# ClockGen.net
KiCad netlist of a schematic drawn in Altium Designer
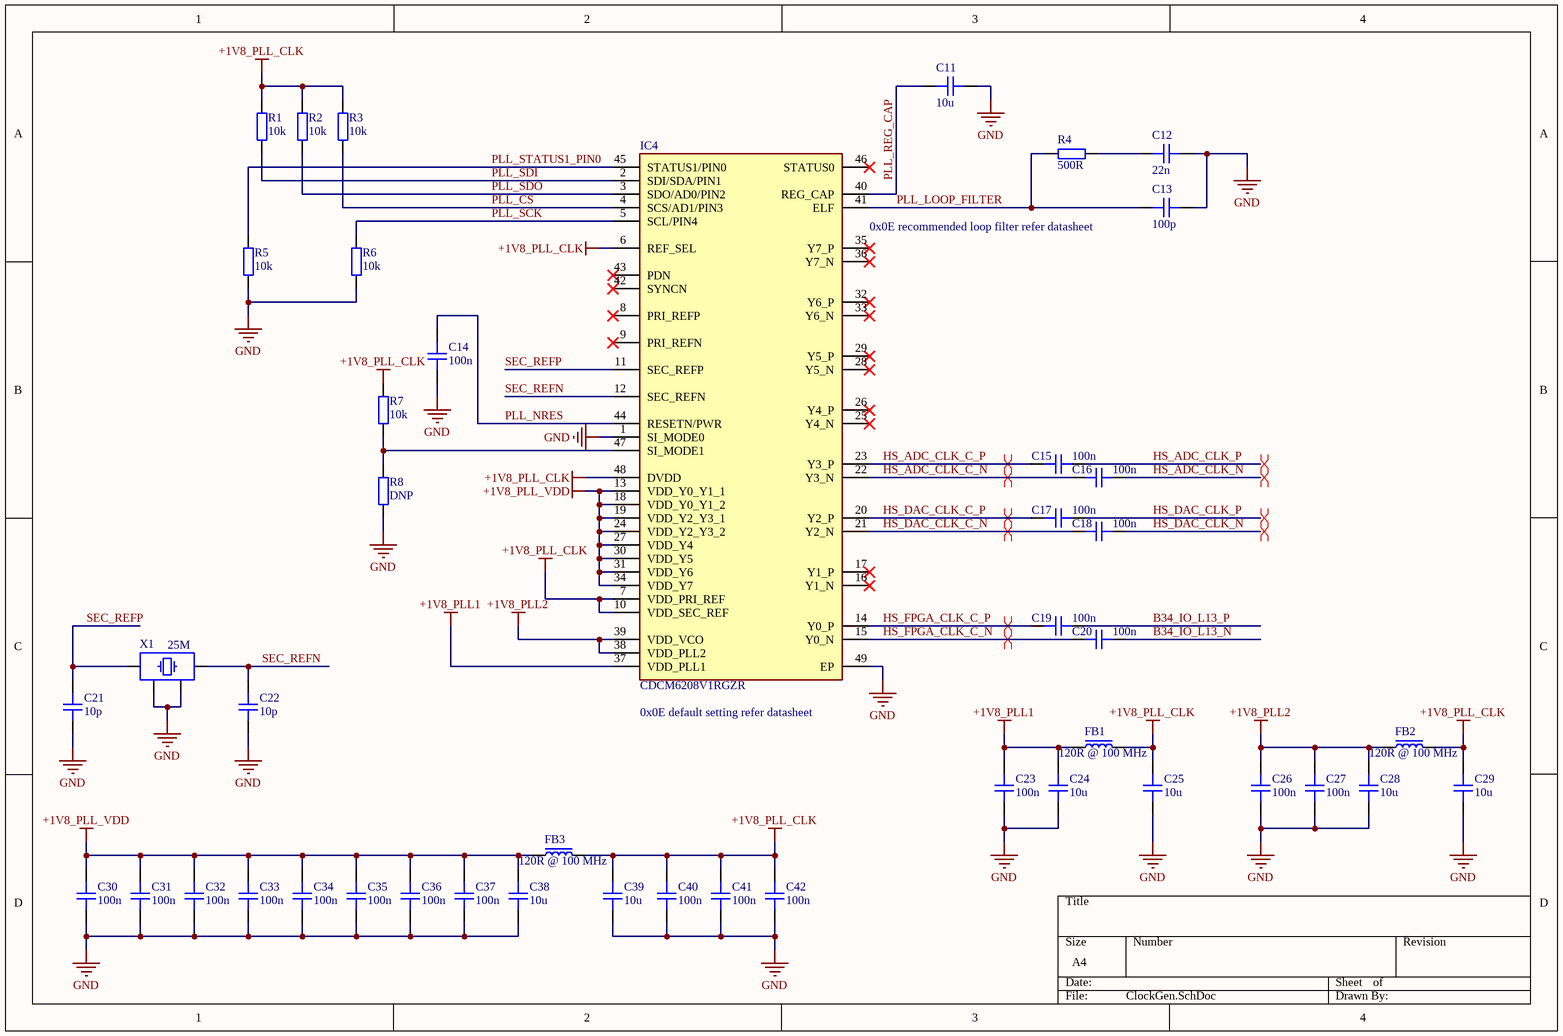
[diagram p0: ClockGen.SchDoc]

(export (version "E")
  (design (tool "Eeschema 10.0.6"))
  (components
    (comp (ref "C11")
      (value "10u")
      (footprint "CAP_0603")
      (description "Capacitor SMD 0603")
      (libsource (lib "Schematic-Lib-PhilsLab") (part "CAP_0603"))
    )
    (comp (ref "C12")
      (value "22n")
      (footprint "CAP_0402")
      (description "Capacitor SMD 0402")
      (libsource (lib "Schematic-Lib-PhilsLab") (part "CAP_0402"))
    )
    (comp (ref "C13")
      (value "100p")
      (footprint "CAP_0402")
      (description "Capacitor SMD 0402")
      (libsource (lib "Schematic-Lib-PhilsLab") (part "CAP_0402"))
    )
    (comp (ref "C14")
      (value "100n")
      (footprint "CAP_0402")
      (description "Capacitor SMD 0402")
      (libsource (lib "Schematic-Lib-PhilsLab") (part "CAP_0402"))
    )
    (comp (ref "C15")
      (value "100n")
      (footprint "CAP_0402")
      (description "Capacitor SMD 0402")
      (libsource (lib "Schematic-Lib-PhilsLab") (part "CAP_0402"))
    )
    (comp (ref "C16")
      (value "100n")
      (footprint "CAP_0402")
      (description "Capacitor SMD 0402")
      (libsource (lib "Schematic-Lib-PhilsLab") (part "CAP_0402"))
    )
    (comp (ref "C17")
      (value "100n")
      (footprint "CAP_0402")
      (description "Capacitor SMD 0402")
      (libsource (lib "Schematic-Lib-PhilsLab") (part "CAP_0402"))
    )
    (comp (ref "C18")
      (value "100n")
      (footprint "CAP_0402")
      (description "Capacitor SMD 0402")
      (libsource (lib "Schematic-Lib-PhilsLab") (part "CAP_0402"))
    )
    (comp (ref "C19")
      (value "100n")
      (footprint "CAP_0402")
      (description "Capacitor SMD 0402")
      (libsource (lib "Schematic-Lib-PhilsLab") (part "CAP_0402"))
    )
    (comp (ref "C20")
      (value "100n")
      (footprint "CAP_0402")
      (description "Capacitor SMD 0402")
      (libsource (lib "Schematic-Lib-PhilsLab") (part "CAP_0402"))
    )
    (comp (ref "C21")
      (value "10p")
      (footprint "CAP_0402")
      (description "Capacitor SMD 0402")
      (libsource (lib "Schematic-Lib-PhilsLab") (part "CAP_0402"))
    )
    (comp (ref "C22")
      (value "10p")
      (footprint "CAP_0402")
      (description "Capacitor SMD 0402")
      (libsource (lib "Schematic-Lib-PhilsLab") (part "CAP_0402"))
    )
    (comp (ref "C23")
      (value "100n")
      (footprint "CAP_0402")
      (description "Capacitor SMD 0402")
      (libsource (lib "Schematic-Lib-PhilsLab") (part "CAP_0402"))
    )
    (comp (ref "C24")
      (value "10u")
      (footprint "CAP_0603")
      (description "Capacitor SMD 0603")
      (libsource (lib "Schematic-Lib-PhilsLab") (part "CAP_0603"))
    )
    (comp (ref "C25")
      (value "10u")
      (footprint "CAP_0603")
      (description "Capacitor SMD 0603")
      (libsource (lib "Schematic-Lib-PhilsLab") (part "CAP_0603"))
    )
    (comp (ref "C26")
      (value "100n")
      (footprint "CAP_0402")
      (description "Capacitor SMD 0402")
      (libsource (lib "Schematic-Lib-PhilsLab") (part "CAP_0402"))
    )
    (comp (ref "C27")
      (value "100n")
      (footprint "CAP_0402")
      (description "Capacitor SMD 0402")
      (libsource (lib "Schematic-Lib-PhilsLab") (part "CAP_0402"))
    )
    (comp (ref "C28")
      (value "10u")
      (footprint "CAP_0603")
      (description "Capacitor SMD 0603")
      (libsource (lib "Schematic-Lib-PhilsLab") (part "CAP_0603"))
    )
    (comp (ref "C29")
      (value "10u")
      (footprint "CAP_0603")
      (description "Capacitor SMD 0603")
      (libsource (lib "Schematic-Lib-PhilsLab") (part "CAP_0603"))
    )
    (comp (ref "C30")
      (value "100n")
      (footprint "CAP_0402")
      (description "Capacitor SMD 0402")
      (libsource (lib "Schematic-Lib-PhilsLab") (part "CAP_0402"))
    )
    (comp (ref "C31")
      (value "100n")
      (footprint "CAP_0402")
      (description "Capacitor SMD 0402")
      (libsource (lib "Schematic-Lib-PhilsLab") (part "CAP_0402"))
    )
    (comp (ref "C32")
      (value "100n")
      (footprint "CAP_0402")
      (description "Capacitor SMD 0402")
      (libsource (lib "Schematic-Lib-PhilsLab") (part "CAP_0402"))
    )
    (comp (ref "C33")
      (value "100n")
      (footprint "CAP_0402")
      (description "Capacitor SMD 0402")
      (libsource (lib "Schematic-Lib-PhilsLab") (part "CAP_0402"))
    )
    (comp (ref "C34")
      (value "100n")
      (footprint "CAP_0402")
      (description "Capacitor SMD 0402")
      (libsource (lib "Schematic-Lib-PhilsLab") (part "CAP_0402"))
    )
    (comp (ref "C35")
      (value "100n")
      (footprint "CAP_0402")
      (description "Capacitor SMD 0402")
      (libsource (lib "Schematic-Lib-PhilsLab") (part "CAP_0402"))
    )
    (comp (ref "C36")
      (value "100n")
      (footprint "CAP_0402")
      (description "Capacitor SMD 0402")
      (libsource (lib "Schematic-Lib-PhilsLab") (part "CAP_0402"))
    )
    (comp (ref "C37")
      (value "100n")
      (footprint "CAP_0402")
      (description "Capacitor SMD 0402")
      (libsource (lib "Schematic-Lib-PhilsLab") (part "CAP_0402"))
    )
    (comp (ref "C38")
      (value "10u")
      (footprint "CAP_0603")
      (description "Capacitor SMD 0603")
      (libsource (lib "Schematic-Lib-PhilsLab") (part "CAP_0603"))
    )
    (comp (ref "C39")
      (value "10u")
      (footprint "CAP_0603")
      (description "Capacitor SMD 0603")
      (libsource (lib "Schematic-Lib-PhilsLab") (part "CAP_0603"))
    )
    (comp (ref "C40")
      (value "100n")
      (footprint "CAP_0402")
      (description "Capacitor SMD 0402")
      (libsource (lib "Schematic-Lib-PhilsLab") (part "CAP_0402"))
    )
    (comp (ref "C41")
      (value "100n")
      (footprint "CAP_0402")
      (description "Capacitor SMD 0402")
      (libsource (lib "Schematic-Lib-PhilsLab") (part "CAP_0402"))
    )
    (comp (ref "C42")
      (value "100n")
      (footprint "CAP_0402")
      (description "Capacitor SMD 0402")
      (libsource (lib "Schematic-Lib-PhilsLab") (part "CAP_0402"))
    )
    (comp (ref "FB1")
      (value "120R @ 100 MHz")
      (footprint "FB_0603")
      (description "Ferrite Bead SMD 0603")
      (libsource (lib "Schematic-Lib-PhilsLab") (part "FB_0603"))
    )
    (comp (ref "FB2")
      (value "120R @ 100 MHz")
      (footprint "FB_0603")
      (description "Ferrite Bead SMD 0603")
      (libsource (lib "Schematic-Lib-PhilsLab") (part "FB_0603"))
    )
    (comp (ref "FB3")
      (value "120R @ 100 MHz")
      (footprint "FB_0603")
      (description "Ferrite Bead SMD 0603")
      (libsource (lib "Schematic-Lib-PhilsLab") (part "FB_0603"))
    )
    (comp (ref "IC4")
      (value "CDCM6208V1RGZR")
      (footprint "JetsonTx2_PCBLib:QFN50P700X700X100-49N-D - duplicate")
      (description "Integrated Circuit")
      (fields (field (name "MOUSER PART NUMBER") "595-CDCM6208V1RGZR"))
      (libsource (lib "JetsonTx2_SCHLib") (part "CDCM6208V1RGZR"))
    )
    (comp (ref "R1")
      (value "10k")
      (footprint "RES_0402")
      (description "Resistor SMD 0402")
      (libsource (lib "Schematic-Lib-PhilsLab") (part "RES_0402"))
    )
    (comp (ref "R2")
      (value "10k")
      (footprint "RES_0402")
      (description "Resistor SMD 0402")
      (libsource (lib "Schematic-Lib-PhilsLab") (part "RES_0402"))
    )
    (comp (ref "R3")
      (value "10k")
      (footprint "RES_0402")
      (description "Resistor SMD 0402")
      (libsource (lib "Schematic-Lib-PhilsLab") (part "RES_0402"))
    )
    (comp (ref "R4")
      (value "500R")
      (footprint "RES_0402")
      (description "Resistor SMD 0402")
      (libsource (lib "Schematic-Lib-PhilsLab") (part "RES_0402"))
    )
    (comp (ref "R5")
      (value "10k")
      (footprint "RES_0402")
      (description "Resistor SMD 0402")
      (libsource (lib "Schematic-Lib-PhilsLab") (part "RES_0402"))
    )
    (comp (ref "R6")
      (value "10k")
      (footprint "RES_0402")
      (description "Resistor SMD 0402")
      (libsource (lib "Schematic-Lib-PhilsLab") (part "RES_0402"))
    )
    (comp (ref "R7")
      (value "10k")
      (footprint "RES_0402")
      (description "Resistor SMD 0402")
      (libsource (lib "Schematic-Lib-PhilsLab") (part "RES_0402"))
    )
    (comp (ref "R8")
      (value "DNP")
      (footprint "RES_0402")
      (description "Resistor SMD 0402")
      (libsource (lib "Schematic-Lib-PhilsLab") (part "RES_0402"))
    )
    (comp (ref "X1")
      (value "25M")
      (footprint "XTAL_3225")
      (description "Crystal SMD 3225")
      (libsource (lib "Schematic-Lib-PhilsLab") (part "XTAL_3225"))
    )
  )
  (nets
    (net (code "1") (name "+1V8_PLL1") (class "Default")
      (node (ref "C23") (pin "1") (pinfunction "1_1") (pintype "passive"))
      (node (ref "C24") (pin "2") (pinfunction "2_2") (pintype "passive"))
      (node (ref "FB1") (pin "1") (pinfunction "1_1") (pintype "passive"))
      (node (ref "IC4") (pin "37") (pinfunction "VDD_PLL1_37") (pintype "passive"))
    )
    (net (code "2") (name "+1V8_PLL2") (class "Default")
      (node (ref "C26") (pin "1") (pinfunction "1_1") (pintype "passive"))
      (node (ref "C27") (pin "1") (pinfunction "1_1") (pintype "passive"))
      (node (ref "C28") (pin "2") (pinfunction "2_2") (pintype "passive"))
      (node (ref "FB2") (pin "1") (pinfunction "1_1") (pintype "passive"))
      (node (ref "IC4") (pin "38") (pinfunction "VDD_PLL2_38") (pintype "passive"))
      (node (ref "IC4") (pin "39") (pinfunction "VDD_VCO_39") (pintype "passive"))
    )
    (net (code "3") (name "+1V8_PLL_CLK") (class "Default")
      (node (ref "C25") (pin "2") (pinfunction "2_2") (pintype "passive"))
      (node (ref "C29") (pin "2") (pinfunction "2_2") (pintype "passive"))
      (node (ref "C39") (pin "2") (pinfunction "2_2") (pintype "passive"))
      (node (ref "C40") (pin "1") (pinfunction "1_1") (pintype "passive"))
      (node (ref "C41") (pin "1") (pinfunction "1_1") (pintype "passive"))
      (node (ref "C42") (pin "1") (pinfunction "1_1") (pintype "passive"))
      (node (ref "FB1") (pin "2") (pinfunction "2_2") (pintype "passive"))
      (node (ref "FB2") (pin "2") (pinfunction "2_2") (pintype "passive"))
      (node (ref "FB3") (pin "2") (pinfunction "2_2") (pintype "passive"))
      (node (ref "IC4") (pin "10") (pinfunction "VDD_SEC_REF_10") (pintype "passive"))
      (node (ref "IC4") (pin "48") (pinfunction "DVDD_48") (pintype "passive"))
      (node (ref "IC4") (pin "6") (pinfunction "REF_SEL_6") (pintype "passive"))
      (node (ref "IC4") (pin "7") (pinfunction "VDD_PRI_REF_7") (pintype "passive"))
      (node (ref "R1") (pin "2") (pinfunction "2_2") (pintype "passive"))
      (node (ref "R2") (pin "2") (pinfunction "2_2") (pintype "passive"))
      (node (ref "R3") (pin "2") (pinfunction "2_2") (pintype "passive"))
      (node (ref "R7") (pin "2") (pinfunction "2_2") (pintype "passive"))
    )
    (net (code "4") (name "+1V8_PLL_VDD") (class "Default")
      (node (ref "C30") (pin "1") (pinfunction "1_1") (pintype "passive"))
      (node (ref "C31") (pin "1") (pinfunction "1_1") (pintype "passive"))
      (node (ref "C32") (pin "1") (pinfunction "1_1") (pintype "passive"))
      (node (ref "C33") (pin "1") (pinfunction "1_1") (pintype "passive"))
      (node (ref "C34") (pin "1") (pinfunction "1_1") (pintype "passive"))
      (node (ref "C35") (pin "1") (pinfunction "1_1") (pintype "passive"))
      (node (ref "C36") (pin "1") (pinfunction "1_1") (pintype "passive"))
      (node (ref "C37") (pin "1") (pinfunction "1_1") (pintype "passive"))
      (node (ref "C38") (pin "2") (pinfunction "2_2") (pintype "passive"))
      (node (ref "FB3") (pin "1") (pinfunction "1_1") (pintype "passive"))
      (node (ref "IC4") (pin "13") (pinfunction "VDD_Y0_Y1_1_13") (pintype "passive"))
      (node (ref "IC4") (pin "18") (pinfunction "VDD_Y0_Y1_2_18") (pintype "passive"))
      (node (ref "IC4") (pin "19") (pinfunction "VDD_Y2_Y3_1_19") (pintype "passive"))
      (node (ref "IC4") (pin "24") (pinfunction "VDD_Y2_Y3_2_24") (pintype "passive"))
      (node (ref "IC4") (pin "27") (pinfunction "VDD_Y4_27") (pintype "passive"))
      (node (ref "IC4") (pin "30") (pinfunction "VDD_Y5_30") (pintype "passive"))
      (node (ref "IC4") (pin "31") (pinfunction "VDD_Y6_31") (pintype "passive"))
      (node (ref "IC4") (pin "34") (pinfunction "VDD_Y7_34") (pintype "passive"))
    )
    (net (code "5") (name "/B34_IO_L13_N") (class "Default")
      (node (ref "C20") (pin "1") (pinfunction "1_1") (pintype "passive"))
    )
    (net (code "6") (name "/B34_IO_L13_P") (class "Default")
      (node (ref "C19") (pin "1") (pinfunction "1_1") (pintype "passive"))
    )
    (net (code "7") (name "/HS_ADC_CLK_C_N") (class "Default")
      (node (ref "C16") (pin "2") (pinfunction "2_2") (pintype "passive"))
      (node (ref "IC4") (pin "22") (pinfunction "Y3_N_22") (pintype "passive"))
    )
    (net (code "8") (name "/HS_ADC_CLK_C_P") (class "Default")
      (node (ref "C15") (pin "2") (pinfunction "2_2") (pintype "passive"))
      (node (ref "IC4") (pin "23") (pinfunction "Y3_P_23") (pintype "passive"))
    )
    (net (code "9") (name "/HS_ADC_CLK_N") (class "Default")
      (node (ref "C16") (pin "1") (pinfunction "1_1") (pintype "passive"))
    )
    (net (code "10") (name "/HS_ADC_CLK_P") (class "Default")
      (node (ref "C15") (pin "1") (pinfunction "1_1") (pintype "passive"))
    )
    (net (code "11") (name "/HS_DAC_CLK_C_N") (class "Default")
      (node (ref "C18") (pin "2") (pinfunction "2_2") (pintype "passive"))
      (node (ref "IC4") (pin "21") (pinfunction "Y2_N_21") (pintype "passive"))
    )
    (net (code "12") (name "/HS_DAC_CLK_C_P") (class "Default")
      (node (ref "C17") (pin "2") (pinfunction "2_2") (pintype "passive"))
      (node (ref "IC4") (pin "20") (pinfunction "Y2_P_20") (pintype "passive"))
    )
    (net (code "13") (name "/HS_DAC_CLK_N") (class "Default")
      (node (ref "C18") (pin "1") (pinfunction "1_1") (pintype "passive"))
    )
    (net (code "14") (name "/HS_DAC_CLK_P") (class "Default")
      (node (ref "C17") (pin "1") (pinfunction "1_1") (pintype "passive"))
    )
    (net (code "15") (name "/HS_FPGA_CLK_C_N") (class "Default")
      (node (ref "C20") (pin "2") (pinfunction "2_2") (pintype "passive"))
      (node (ref "IC4") (pin "15") (pinfunction "Y0_N_15") (pintype "passive"))
    )
    (net (code "16") (name "/HS_FPGA_CLK_C_P") (class "Default")
      (node (ref "C19") (pin "2") (pinfunction "2_2") (pintype "passive"))
      (node (ref "IC4") (pin "14") (pinfunction "Y0_P_14") (pintype "passive"))
    )
    (net (code "17") (name "/PLL_CS") (class "Default")
      (node (ref "IC4") (pin "4") (pinfunction "SCS/AD1/PIN3_4") (pintype "passive"))
      (node (ref "R3") (pin "1") (pinfunction "1_1") (pintype "passive"))
    )
    (net (code "18") (name "/PLL_LOOP_FILTER") (class "Default")
      (node (ref "C13") (pin "2") (pinfunction "2_2") (pintype "passive"))
      (node (ref "IC4") (pin "41") (pinfunction "ELF_41") (pintype "passive"))
      (node (ref "R4") (pin "2") (pinfunction "2_2") (pintype "passive"))
    )
    (net (code "19") (name "/PLL_NRES") (class "Default")
      (node (ref "C14") (pin "2") (pinfunction "2_2") (pintype "passive"))
      (node (ref "IC4") (pin "44") (pinfunction "RESETN/PWR_44") (pintype "passive"))
    )
    (net (code "20") (name "/PLL_REG_CAP") (class "Default")
      (node (ref "C11") (pin "1") (pinfunction "1_1") (pintype "passive"))
      (node (ref "IC4") (pin "40") (pinfunction "REG_CAP_40") (pintype "passive"))
    )
    (net (code "21") (name "/PLL_SCK") (class "Default")
      (node (ref "IC4") (pin "5") (pinfunction "SCL/PIN4_5") (pintype "passive"))
      (node (ref "R6") (pin "2") (pinfunction "2_2") (pintype "passive"))
    )
    (net (code "22") (name "/PLL_SDI") (class "Default")
      (node (ref "IC4") (pin "2") (pinfunction "SDI/SDA/PIN1_2") (pintype "passive"))
      (node (ref "R1") (pin "1") (pinfunction "1_1") (pintype "passive"))
    )
    (net (code "23") (name "/PLL_SDO") (class "Default")
      (node (ref "IC4") (pin "3") (pinfunction "SDO/AD0/PIN2_3") (pintype "passive"))
      (node (ref "R2") (pin "1") (pinfunction "1_1") (pintype "passive"))
    )
    (net (code "24") (name "/PLL_STATUS1_PIN0") (class "Default")
      (node (ref "IC4") (pin "45") (pinfunction "STATUS1/PIN0_45") (pintype "passive"))
      (node (ref "R5") (pin "2") (pinfunction "2_2") (pintype "passive"))
    )
    (net (code "25") (name "/SEC_REFN") (class "Default")
      (node (ref "C22") (pin "1") (pinfunction "1_1") (pintype "passive"))
      (node (ref "IC4") (pin "12") (pinfunction "SEC_REFN_12") (pintype "passive"))
      (node (ref "X1") (pin "3") (pinfunction "3_3") (pintype "passive"))
    )
    (net (code "26") (name "/SEC_REFP") (class "Default")
      (node (ref "C21") (pin "1") (pinfunction "1_1") (pintype "passive"))
      (node (ref "IC4") (pin "11") (pinfunction "SEC_REFP_11") (pintype "passive"))
      (node (ref "X1") (pin "1") (pinfunction "1_1") (pintype "passive"))
    )
    (net (code "27") (name "GND") (class "Default")
      (node (ref "C11") (pin "2") (pinfunction "2_2") (pintype "passive"))
      (node (ref "C12") (pin "1") (pinfunction "1_1") (pintype "passive"))
      (node (ref "C13") (pin "1") (pinfunction "1_1") (pintype "passive"))
      (node (ref "C14") (pin "1") (pinfunction "1_1") (pintype "passive"))
      (node (ref "C21") (pin "2") (pinfunction "2_2") (pintype "passive"))
      (node (ref "C22") (pin "2") (pinfunction "2_2") (pintype "passive"))
      (node (ref "C23") (pin "2") (pinfunction "2_2") (pintype "passive"))
      (node (ref "C24") (pin "1") (pinfunction "1_1") (pintype "passive"))
      (node (ref "C25") (pin "1") (pinfunction "1_1") (pintype "passive"))
      (node (ref "C26") (pin "2") (pinfunction "2_2") (pintype "passive"))
      (node (ref "C27") (pin "2") (pinfunction "2_2") (pintype "passive"))
      (node (ref "C28") (pin "1") (pinfunction "1_1") (pintype "passive"))
      (node (ref "C29") (pin "1") (pinfunction "1_1") (pintype "passive"))
      (node (ref "C30") (pin "2") (pinfunction "2_2") (pintype "passive"))
      (node (ref "C31") (pin "2") (pinfunction "2_2") (pintype "passive"))
      (node (ref "C32") (pin "2") (pinfunction "2_2") (pintype "passive"))
      (node (ref "C33") (pin "2") (pinfunction "2_2") (pintype "passive"))
      (node (ref "C34") (pin "2") (pinfunction "2_2") (pintype "passive"))
      (node (ref "C35") (pin "2") (pinfunction "2_2") (pintype "passive"))
      (node (ref "C36") (pin "2") (pinfunction "2_2") (pintype "passive"))
      (node (ref "C37") (pin "2") (pinfunction "2_2") (pintype "passive"))
      (node (ref "C38") (pin "1") (pinfunction "1_1") (pintype "passive"))
      (node (ref "C39") (pin "1") (pinfunction "1_1") (pintype "passive"))
      (node (ref "C40") (pin "2") (pinfunction "2_2") (pintype "passive"))
      (node (ref "C41") (pin "2") (pinfunction "2_2") (pintype "passive"))
      (node (ref "C42") (pin "2") (pinfunction "2_2") (pintype "passive"))
      (node (ref "IC4") (pin "1") (pinfunction "SI_MODE0_1") (pintype "passive"))
      (node (ref "IC4") (pin "49") (pinfunction "EP_49") (pintype "passive"))
      (node (ref "R5") (pin "1") (pinfunction "1_1") (pintype "passive"))
      (node (ref "R6") (pin "1") (pinfunction "1_1") (pintype "passive"))
      (node (ref "R8") (pin "1") (pinfunction "1_1") (pintype "passive"))
      (node (ref "X1") (pin "2") (pinfunction "2_2") (pintype "passive"))
      (node (ref "X1") (pin "4") (pinfunction "4_4") (pintype "passive"))
    )
    (net (code "28") (name "Net-(C12-Pad2)") (class "Default")
      (node (ref "C12") (pin "2") (pinfunction "2_2") (pintype "passive"))
      (node (ref "R4") (pin "1") (pinfunction "1_1") (pintype "passive"))
    )
    (net (code "29") (name "Net-(IC4-SI_MODE1)") (class "Default")
      (node (ref "IC4") (pin "47") (pinfunction "SI_MODE1_47") (pintype "passive"))
      (node (ref "R7") (pin "1") (pinfunction "1_1") (pintype "passive"))
      (node (ref "R8") (pin "2") (pinfunction "2_2") (pintype "passive"))
    )
    (net (code "30") (name "unconnected-(IC4-PDN-Pad43)") (class "Default")
      (node (ref "IC4") (pin "43") (pinfunction "PDN_43") (pintype "passive+no_connect"))
    )
    (net (code "31") (name "unconnected-(IC4-PRI_REFN-Pad9)") (class "Default")
      (node (ref "IC4") (pin "9") (pinfunction "PRI_REFN_9") (pintype "passive+no_connect"))
    )
    (net (code "32") (name "unconnected-(IC4-PRI_REFP-Pad8)") (class "Default")
      (node (ref "IC4") (pin "8") (pinfunction "PRI_REFP_8") (pintype "passive+no_connect"))
    )
    (net (code "33") (name "unconnected-(IC4-STATUS0-Pad46)") (class "Default")
      (node (ref "IC4") (pin "46") (pinfunction "STATUS0_46") (pintype "passive+no_connect"))
    )
    (net (code "34") (name "unconnected-(IC4-SYNCN-Pad42)") (class "Default")
      (node (ref "IC4") (pin "42") (pinfunction "SYNCN_42") (pintype "passive+no_connect"))
    )
    (net (code "35") (name "unconnected-(IC4-Y1_N-Pad16)") (class "Default")
      (node (ref "IC4") (pin "16") (pinfunction "Y1_N_16") (pintype "passive+no_connect"))
    )
    (net (code "36") (name "unconnected-(IC4-Y1_P-Pad17)") (class "Default")
      (node (ref "IC4") (pin "17") (pinfunction "Y1_P_17") (pintype "passive+no_connect"))
    )
    (net (code "37") (name "unconnected-(IC4-Y4_N-Pad25)") (class "Default")
      (node (ref "IC4") (pin "25") (pinfunction "Y4_N_25") (pintype "passive+no_connect"))
    )
    (net (code "38") (name "unconnected-(IC4-Y4_P-Pad26)") (class "Default")
      (node (ref "IC4") (pin "26") (pinfunction "Y4_P_26") (pintype "passive+no_connect"))
    )
    (net (code "39") (name "unconnected-(IC4-Y5_N-Pad28)") (class "Default")
      (node (ref "IC4") (pin "28") (pinfunction "Y5_N_28") (pintype "passive+no_connect"))
    )
    (net (code "40") (name "unconnected-(IC4-Y5_P-Pad29)") (class "Default")
      (node (ref "IC4") (pin "29") (pinfunction "Y5_P_29") (pintype "passive+no_connect"))
    )
    (net (code "41") (name "unconnected-(IC4-Y6_N-Pad33)") (class "Default")
      (node (ref "IC4") (pin "33") (pinfunction "Y6_N_33") (pintype "passive+no_connect"))
    )
    (net (code "42") (name "unconnected-(IC4-Y6_P-Pad32)") (class "Default")
      (node (ref "IC4") (pin "32") (pinfunction "Y6_P_32") (pintype "passive+no_connect"))
    )
    (net (code "43") (name "unconnected-(IC4-Y7_N-Pad36)") (class "Default")
      (node (ref "IC4") (pin "36") (pinfunction "Y7_N_36") (pintype "passive+no_connect"))
    )
    (net (code "44") (name "unconnected-(IC4-Y7_P-Pad35)") (class "Default")
      (node (ref "IC4") (pin "35") (pinfunction "Y7_P_35") (pintype "passive+no_connect"))
    )
  )
)
